# TIDA-010042-E2_Power_Stage_Pg3.net
KiCad netlist of a schematic drawn in Altium Designer
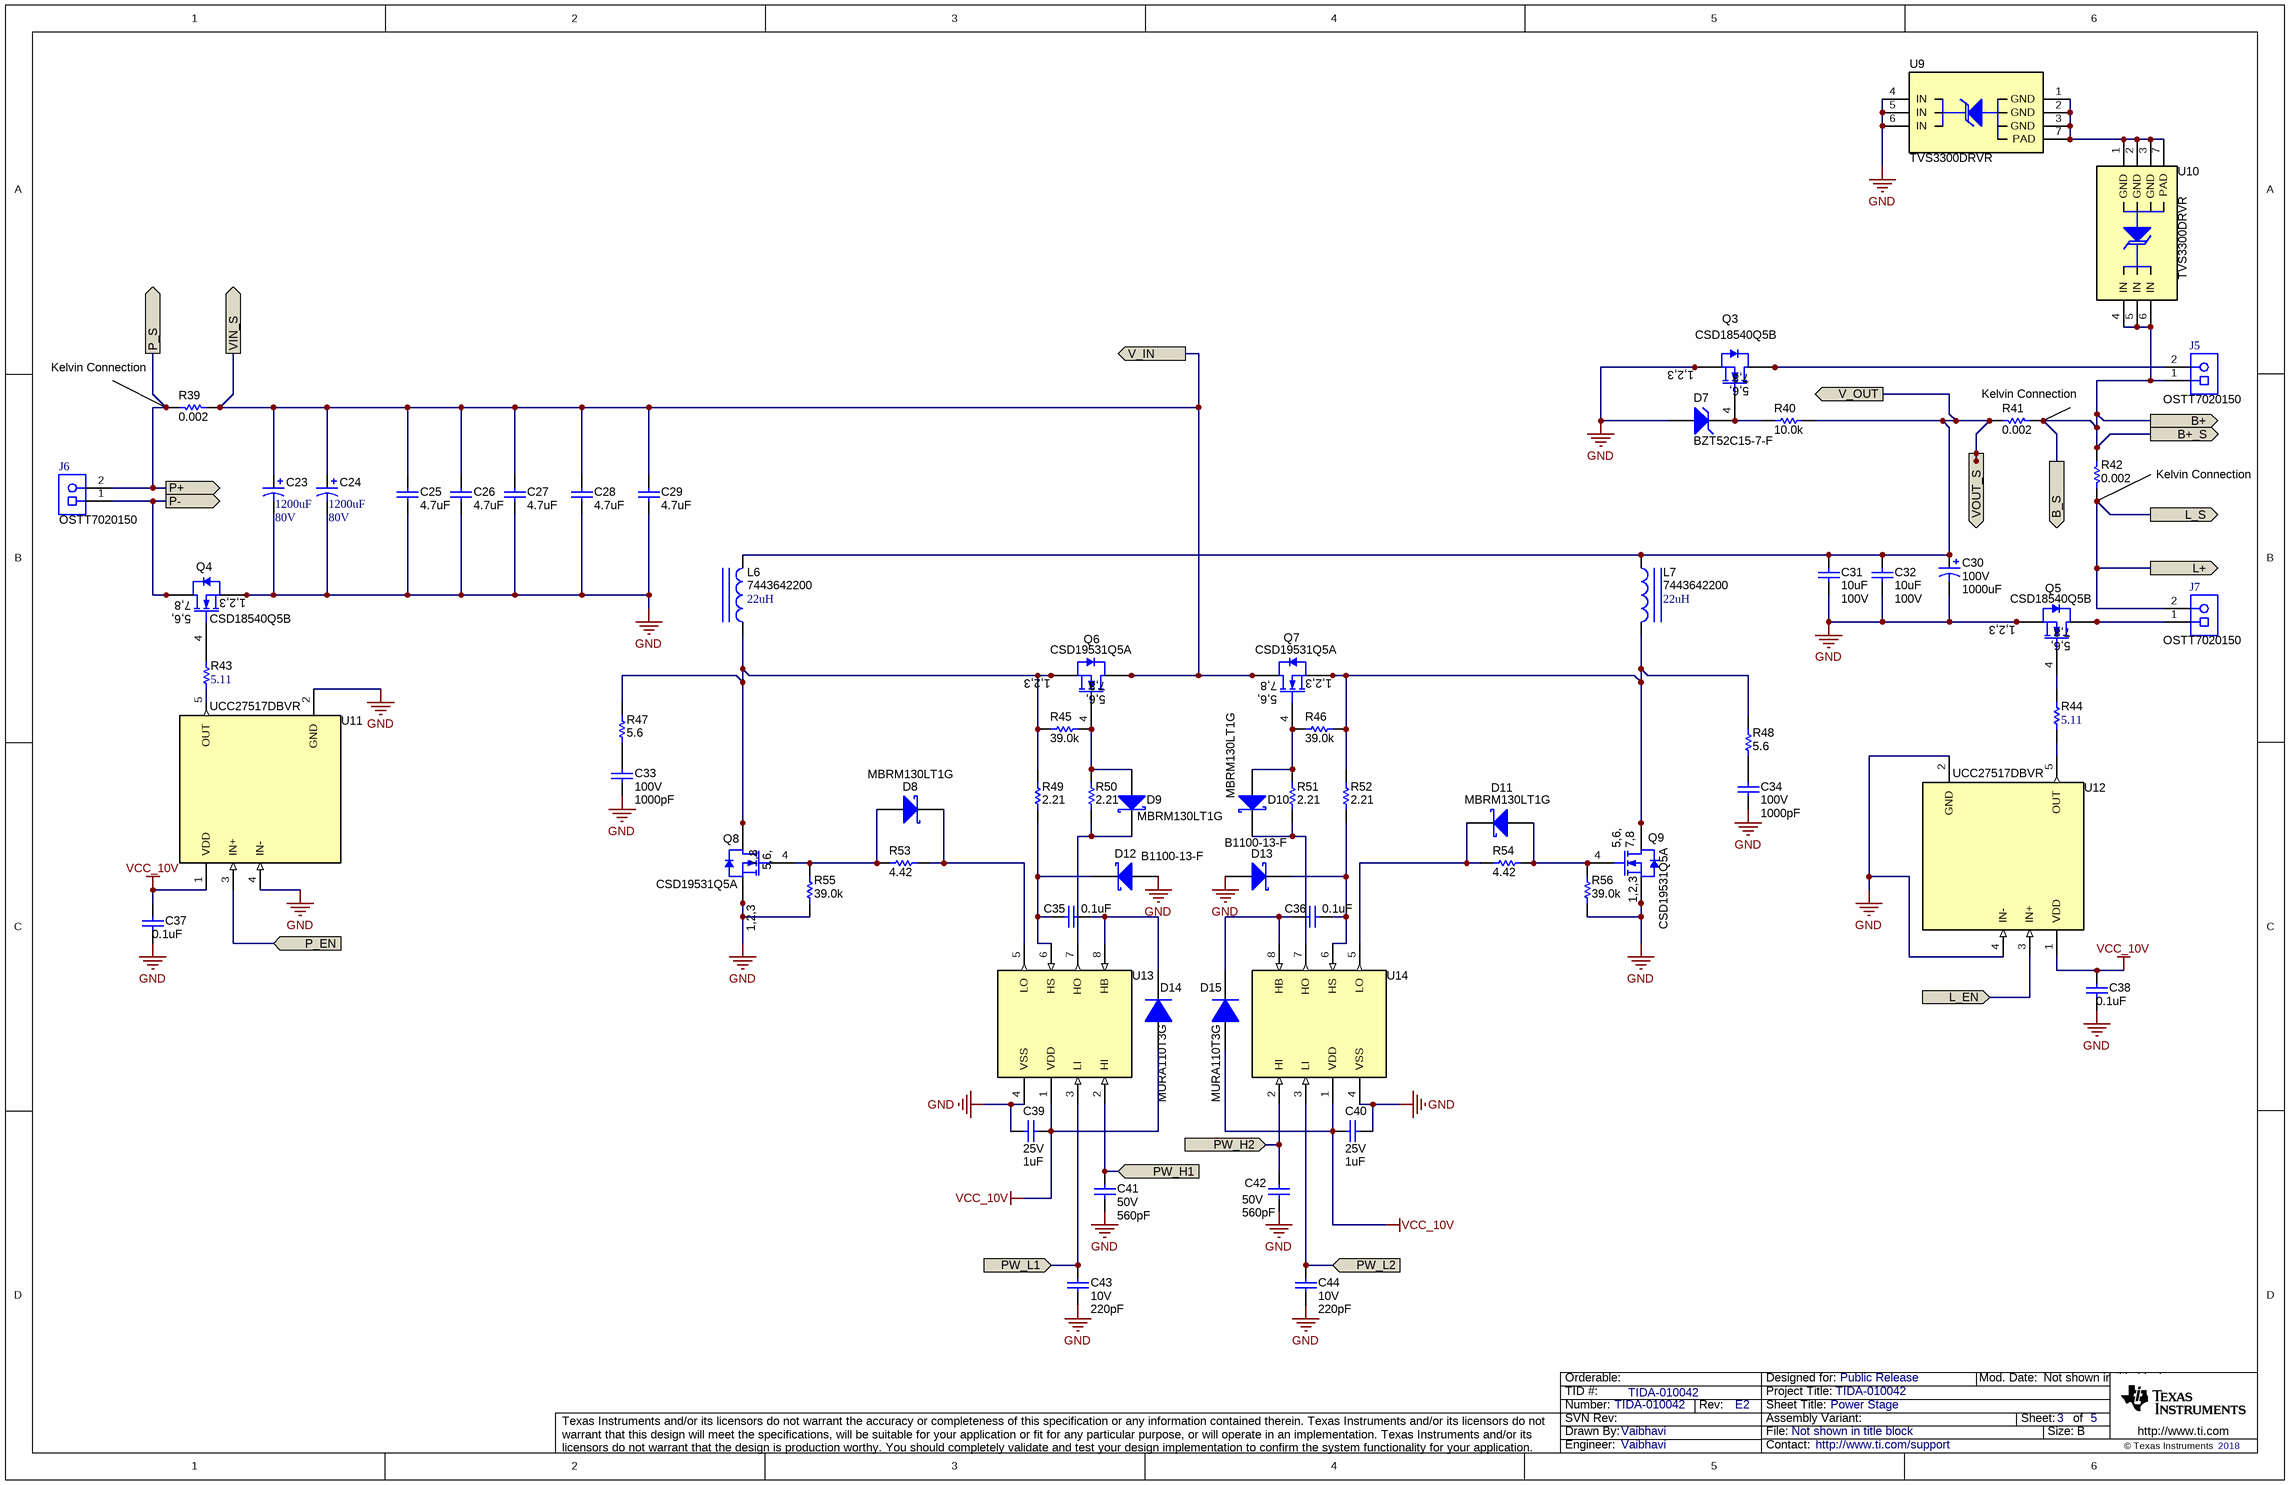
[diagram p0: TIDA-010042-E2_Power Stage_Pg3.SchDoc]

(export (version "E")
  (design (tool "Eeschema 10.0.6"))
  (components
    (comp (ref "C23")
      (value "1200uF")
      (footprint "KYB_1800x3150")
      (description "CAP, AL, 1200 uF, 80 V, +/- 20%, 0.02 ohm, TH")
      (fields
        (field (name "MANUFACTURER") "Chemi-Con")
        (field (name "PARTNUMBER") "EKYB800ELL122MMN3S")
        (field (name "VDC_V") "80V")
        (field (name "PUBLISHER") "Texas Instruments")
      )
      (libsource (lib "Altium Vault - TI") (part "CMP-0009878-2"))
    )
    (comp (ref "C24")
      (value "1200uF")
      (footprint "KYB_1800x3150")
      (description "CAP, AL, 1200 uF, 80 V, +/- 20%, 0.02 ohm, TH")
      (fields
        (field (name "MANUFACTURER") "Chemi-Con")
        (field (name "PARTNUMBER") "EKYB800ELL122MMN3S")
        (field (name "VDC_V") "80V")
        (field (name "PUBLISHER") "Texas Instruments")
      )
      (libsource (lib "Altium Vault - TI") (part "CMP-0009878-2"))
    )
    (comp (ref "C25")
      (value "Capacitor")
      (footprint "2220_250")
      (description "CAP, CERM, 4.7 uF, 100 V, +/- 20%, X7R, AEC-Q200 Grade 1,")
      (fields
        (field (name "PARTNUMBER") "CGA9N2X7R2A475M230KA")
        (field (name "VALUEDISPLAYED") "4.7uF")
        (field (name "MANUFACTURER") "TDK")
        (field (name "PUBLISHER") "Texas Instruments")
      )
      (libsource (lib "Altium Vault - TI") (part "Capacitor"))
    )
    (comp (ref "C26")
      (value "Capacitor")
      (footprint "2220_250")
      (description "CAP, CERM, 4.7 uF, 100 V, +/- 20%, X7R, AEC-Q200 Grade 1,")
      (fields
        (field (name "PARTNUMBER") "CGA9N2X7R2A475M230KA")
        (field (name "VALUEDISPLAYED") "4.7uF")
        (field (name "MANUFACTURER") "TDK")
        (field (name "PUBLISHER") "Texas Instruments")
      )
      (libsource (lib "Altium Vault - TI") (part "Capacitor"))
    )
    (comp (ref "C27")
      (value "Capacitor")
      (footprint "2220_250")
      (description "CAP, CERM, 4.7 uF, 100 V, +/- 20%, X7R, AEC-Q200 Grade 1,")
      (fields
        (field (name "PARTNUMBER") "CGA9N2X7R2A475M230KA")
        (field (name "VALUEDISPLAYED") "4.7uF")
        (field (name "MANUFACTURER") "TDK")
        (field (name "PUBLISHER") "Texas Instruments")
      )
      (libsource (lib "Altium Vault - TI") (part "Capacitor"))
    )
    (comp (ref "C28")
      (value "Capacitor")
      (footprint "2220_250")
      (description "CAP, CERM, 4.7 uF, 100 V, +/- 20%, X7R, AEC-Q200 Grade 1,")
      (fields
        (field (name "PARTNUMBER") "CGA9N2X7R2A475M230KA")
        (field (name "VALUEDISPLAYED") "4.7uF")
        (field (name "MANUFACTURER") "TDK")
        (field (name "PUBLISHER") "Texas Instruments")
      )
      (libsource (lib "Altium Vault - TI") (part "Capacitor"))
    )
    (comp (ref "C29")
      (value "Capacitor")
      (footprint "2220_250")
      (description "CAP, CERM, 4.7 uF, 100 V, +/- 20%, X7R, AEC-Q200 Grade 1,")
      (fields
        (field (name "PARTNUMBER") "CGA9N2X7R2A475M230KA")
        (field (name "VALUEDISPLAYED") "4.7uF")
        (field (name "MANUFACTURER") "TDK")
        (field (name "PUBLISHER") "Texas Instruments")
      )
      (libsource (lib "Altium Vault - TI") (part "Capacitor"))
    )
    (comp (ref "C30")
      (value "UVR2A102MHD")
      (footprint "VR_1800x4000")
      (description "CAP, AL, 1000 uF, 100 V, +/- 20%, TH")
      (fields
        (field (name "MANUFACTURER") "Nichicon")
        (field (name "VDC_V") "100V")
        (field (name "VALUEDISPLAYED") "1000uF")
        (field (name "PUBLISHER") "Texas Instruments")
      )
      (libsource (lib "Altium Vault - TI") (part "Cap_Polarized"))
    )
    (comp (ref "C31")
      (value "22201C106MAT2A")
      (footprint "2220_280")
      (description "CAP, CERM, 10 uF, 100 V, +/- 20%, X7R, 2220")
      (fields
        (field (name "VALUEDISPLAYED") "10uF")
        (field (name "MANUFACTURER") "AVX")
        (field (name "VDC_V") "100V")
        (field (name "PUBLISHER") "Texas Instruments")
      )
      (libsource (lib "Altium Vault - TI") (part "Capacitor"))
    )
    (comp (ref "C32")
      (value "22201C106MAT2A")
      (footprint "2220_280")
      (description "CAP, CERM, 10 uF, 100 V, +/- 20%, X7R, 2220")
      (fields
        (field (name "VALUEDISPLAYED") "10uF")
        (field (name "MANUFACTURER") "AVX")
        (field (name "VDC_V") "100V")
        (field (name "PUBLISHER") "Texas Instruments")
      )
      (libsource (lib "Altium Vault - TI") (part "Capacitor"))
    )
    (comp (ref "C33")
      (value "06031C102JAT2A")
      (footprint "0603")
      (description "CAP, CERM, 1000 pF, 100 V, +/- 5%, X7R, 0603")
      (fields
        (field (name "MANUFACTURER") "AVX")
        (field (name "VDC_V") "100V")
        (field (name "VALUEDISPLAYED") "1000pF")
        (field (name "PUBLISHER") "Texas Instruments")
      )
      (libsource (lib "Altium Vault - TI") (part "Capacitor"))
    )
    (comp (ref "C34")
      (value "06031C102JAT2A")
      (footprint "0603")
      (description "CAP, CERM, 1000 pF, 100 V, +/- 5%, X7R, 0603")
      (fields
        (field (name "MANUFACTURER") "AVX")
        (field (name "VDC_V") "100V")
        (field (name "VALUEDISPLAYED") "1000pF")
        (field (name "PUBLISHER") "Texas Instruments")
      )
      (libsource (lib "Altium Vault - TI") (part "Capacitor"))
    )
    (comp (ref "C35")
      (value "C0805C104K3RACAUTO")
      (footprint "0805_HV")
      (description "CAP CER 0.1UF 16V X7R 0805")
      (fields
        (field (name "MANUFACTURER") "Wurth Electronics Inc.")
        (field (name "PARTNUMBER") "885012207045")
        (field (name "VALUEDISPLAYED") "0.1uF")
        (field (name "PUBLISHER") "Texas Instruments")
      )
      (libsource (lib "Altium Vault - TI") (part "CMP-0007567-2"))
    )
    (comp (ref "C36")
      (value "C0805C104K3RACAUTO")
      (footprint "0805_HV")
      (description "CAP CER 0.1UF 16V X7R 0805")
      (fields
        (field (name "MANUFACTURER") "Wurth Electronics Inc.")
        (field (name "PARTNUMBER") "885012207045")
        (field (name "VALUEDISPLAYED") "0.1uF")
        (field (name "PUBLISHER") "Texas Instruments")
      )
      (libsource (lib "Altium Vault - TI") (part "CMP-0007567-2"))
    )
    (comp (ref "C37")
      (value "GMK107BJ104KAHT")
      (footprint "0603")
      (description "CAP CER 0.1UF 25V X5R 0603")
      (fields
        (field (name "MANUFACTURER") "Taiyo Yuden")
        (field (name "PARTNUMBER") "TMK107BJ104KA-T")
        (field (name "VALUEDISPLAYED") "0.1uF")
        (field (name "PUBLISHER") "Texas Instruments")
      )
      (libsource (lib "Altium Vault - TI") (part "CMP-0007044-5"))
    )
    (comp (ref "C38")
      (value "GMK107BJ104KAHT")
      (footprint "0603")
      (description "CAP CER 0.1UF 25V X5R 0603")
      (fields
        (field (name "MANUFACTURER") "Taiyo Yuden")
        (field (name "PARTNUMBER") "TMK107BJ104KA-T")
        (field (name "VALUEDISPLAYED") "0.1uF")
        (field (name "PUBLISHER") "Texas Instruments")
      )
      (libsource (lib "Altium Vault - TI") (part "CMP-0007044-5"))
    )
    (comp (ref "C39")
      (value "08053C105KAT2A")
      (footprint "0805_HV")
      (description "CAP CER 1UF 25V X7R 0805")
      (fields
        (field (name "MANUFACTURER") "Wurth Electronics Inc.")
        (field (name "PARTNUMBER") "885012207078")
        (field (name "VDC_V") "25V")
        (field (name "VALUEDISPLAYED") "1uF")
        (field (name "PUBLISHER") "Texas Instruments")
      )
      (libsource (lib "Altium Vault - TI") (part "CMP-0007728-2"))
    )
    (comp (ref "C40")
      (value "08053C105KAT2A")
      (footprint "0805_HV")
      (description "CAP CER 1UF 25V X7R 0805")
      (fields
        (field (name "MANUFACTURER") "Wurth Electronics Inc.")
        (field (name "PARTNUMBER") "885012207078")
        (field (name "VDC_V") "25V")
        (field (name "VALUEDISPLAYED") "1uF")
        (field (name "PUBLISHER") "Texas Instruments")
      )
      (libsource (lib "Altium Vault - TI") (part "CMP-0007728-2"))
    )
    (comp (ref "C41")
      (value "C0603C561J5GACTU")
      (footprint "0603")
      (description "CAP, CERM, 560 pF, 50 V, +/- 5%, C0G/NP0, 0603")
      (fields
        (field (name "MANUFACTURER") "Kemet")
        (field (name "VDC_V") "50V")
        (field (name "VALUEDISPLAYED") "560pF")
        (field (name "PUBLISHER") "Texas Instruments")
      )
      (libsource (lib "Altium Vault - TI") (part "Capacitor"))
    )
    (comp (ref "C42")
      (value "C0603C561J5GACTU")
      (footprint "0603")
      (description "CAP, CERM, 560 pF, 50 V, +/- 5%, C0G/NP0, 0603")
      (fields
        (field (name "MANUFACTURER") "Kemet")
        (field (name "VDC_V") "50V")
        (field (name "VALUEDISPLAYED") "560pF")
        (field (name "PUBLISHER") "Texas Instruments")
      )
      (libsource (lib "Altium Vault - TI") (part "Capacitor"))
    )
    (comp (ref "C43")
      (value "CL10C221FB8NNNC")
      (footprint "0603")
      (description "CAP CER 220PF 10V C0G/NP0 0603")
      (fields
        (field (name "MANUFACTURER") "Wurth Electronics Inc.")
        (field (name "PARTNUMBER") "885012006010")
        (field (name "VDC_V") "10V")
        (field (name "VALUEDISPLAYED") "220pF")
        (field (name "PUBLISHER") "Texas Instruments")
      )
      (libsource (lib "Altium Vault - TI") (part "CMP-0007197-4"))
    )
    (comp (ref "C44")
      (value "CL10C221FB8NNNC")
      (footprint "0603")
      (description "CAP CER 220PF 10V C0G/NP0 0603")
      (fields
        (field (name "MANUFACTURER") "Wurth Electronics Inc.")
        (field (name "PARTNUMBER") "885012006010")
        (field (name "VDC_V") "10V")
        (field (name "VALUEDISPLAYED") "220pF")
        (field (name "PUBLISHER") "Texas Instruments")
      )
      (libsource (lib "Altium Vault - TI") (part "CMP-0007197-4"))
    )
    (comp (ref "D7")
      (value "BZT52C15-7-F")
      (footprint "SOD-123")
      (description "Diode, Zener, 15 V, 370 mW, AEC-Q101, SOD-123")
      (fields (field (name "MANUFACTURER") "Diodes Inc.") (field (name "PUBLISHER") "Texas Instruments"))
      (libsource (lib "Altium Vault - TI") (part "Zener"))
    )
    (comp (ref "D8")
      (value "MBRM130LT1G")
      (footprint "POWERMITE")
      (description "Diode, Schottky, 30 V, 1 A, POWERMITE")
      (fields (field (name "MANUFACTURER") "ON Semiconductor") (field (name "PUBLISHER") "Texas Instruments"))
      (libsource (lib "Altium Vault - TI") (part "DIODE_SCHOTTKY"))
    )
    (comp (ref "D9")
      (value "MBRM130LT1G")
      (footprint "POWERMITE")
      (description "Diode, Schottky, 30 V, 1 A, POWERMITE")
      (fields (field (name "MANUFACTURER") "ON Semiconductor") (field (name "PUBLISHER") "Texas Instruments"))
      (libsource (lib "Altium Vault - TI") (part "DIODE_SCHOTTKY"))
    )
    (comp (ref "D10")
      (value "MBRM130LT1G")
      (footprint "POWERMITE")
      (description "Diode, Schottky, 30 V, 1 A, POWERMITE")
      (fields (field (name "MANUFACTURER") "ON Semiconductor") (field (name "PUBLISHER") "Texas Instruments"))
      (libsource (lib "Altium Vault - TI") (part "DIODE_SCHOTTKY"))
    )
    (comp (ref "D11")
      (value "MBRM130LT1G")
      (footprint "POWERMITE")
      (description "Diode, Schottky, 30 V, 1 A, POWERMITE")
      (fields (field (name "MANUFACTURER") "ON Semiconductor") (field (name "PUBLISHER") "Texas Instruments"))
      (libsource (lib "Altium Vault - TI") (part "DIODE_SCHOTTKY"))
    )
    (comp (ref "D12")
      (value "B1100-13-F")
      (footprint "SMA")
      (description "Diode, Schottky, 100 V, 1 A, SMA")
      (fields (field (name "MANUFACTURER") "Diodes Inc.") (field (name "PUBLISHER") "Texas Instruments"))
      (libsource (lib "Altium Vault - TI") (part "DIODE_SCHOTTKY"))
    )
    (comp (ref "D13")
      (value "B1100-13-F")
      (footprint "SMA")
      (description "Diode, Schottky, 100 V, 1 A, SMA")
      (fields (field (name "MANUFACTURER") "Diodes Inc.") (field (name "PUBLISHER") "Texas Instruments"))
      (libsource (lib "Altium Vault - TI") (part "DIODE_SCHOTTKY"))
    )
    (comp (ref "D14")
      (value "MURA110T3G")
      (footprint "SMA")
      (description "Diode, Ultrafast, 100 V, 2 A, SMA")
      (fields (field (name "MANUFACTURER") "ON Semiconductor") (field (name "PUBLISHER") "Texas Instruments"))
      (libsource (lib "Altium Vault - TI") (part "DIODE"))
    )
    (comp (ref "D15")
      (value "MURA110T3G")
      (footprint "SMA")
      (description "Diode, Ultrafast, 100 V, 2 A, SMA")
      (fields (field (name "MANUFACTURER") "ON Semiconductor") (field (name "PUBLISHER") "Texas Instruments"))
      (libsource (lib "Altium Vault - TI") (part "DIODE"))
    )
    (comp (ref "J5")
      (value "OSTT7020150")
      (footprint "On-Shore_OSTT7020150")
      (description "Terminal Block, 6.35mm, 2x1, TH")
      (fields
        (field (name "MANUFACTURER") "On-Shore Technology")
        (field (name "PUBLISHER") "Texas Instruments")
      )
      (libsource (lib "Altium Vault - TI") (part "Receptacle_2x1"))
    )
    (comp (ref "J6")
      (value "OSTT7020150")
      (footprint "On-Shore_OSTT7020150")
      (description "Terminal Block, 6.35mm, 2x1, TH")
      (fields
        (field (name "MANUFACTURER") "On-Shore Technology")
        (field (name "PUBLISHER") "Texas Instruments")
      )
      (libsource (lib "") (part "Receptacle_2x1_1"))
    )
    (comp (ref "J7")
      (value "OSTT7020150")
      (footprint "On-Shore_OSTT7020150")
      (description "Terminal Block, 6.35mm, 2x1, TH")
      (fields
        (field (name "MANUFACTURER") "On-Shore Technology")
        (field (name "PUBLISHER") "Texas Instruments")
      )
      (libsource (lib "Altium Vault - TI") (part "Receptacle_2x1"))
    )
    (comp (ref "L6")
      (value "7443642200")
      (footprint "WE-HCF_2818")
      (description "Inductor, Shielded, Ferrite, 22 uH, 18 A, 0.00264 ohm, SMD")
      (fields
        (field (name "MANUFACTURER") "Wurth Elektronik")
        (field (name "VALUEDISPLAYED") "22uH")
        (field (name "PUBLISHER") "Texas Instruments")
      )
      (libsource (lib "Altium Vault - TI") (part "CMP-0064487-2"))
    )
    (comp (ref "L7")
      (value "7443642200")
      (footprint "WE-HCF_2818")
      (description "Inductor, Shielded, Ferrite, 22 uH, 18 A, 0.00264 ohm, SMD")
      (fields
        (field (name "MANUFACTURER") "Wurth Elektronik")
        (field (name "VALUEDISPLAYED") "22uH")
        (field (name "PUBLISHER") "Texas Instruments")
      )
      (libsource (lib "Altium Vault - TI") (part "CMP-0064487-2"))
    )
    (comp (ref "Q3")
      (value "CSD18540Q5B")
      (footprint "DNK0008A")
      (description "MOSFET, N-CH, 60 V, 100 A, DNK0008A (VSON-CLIP-8)")
      (fields (field (name "MANUFACTURER") "Texas Instruments"))
      (libsource (lib "Altium Vault - TI") (part "MOSFET_N_D56789G4S123"))
    )
    (comp (ref "Q4")
      (value "CSD18540Q5B")
      (footprint "DNK0008A")
      (description "MOSFET, N-CH, 60 V, 100 A, DNK0008A (VSON-CLIP-8)")
      (fields (field (name "MANUFACTURER") "Texas Instruments"))
      (libsource (lib "Altium Vault - TI") (part "MOSFET_N_D56789G4S123"))
    )
    (comp (ref "Q5")
      (value "CSD18540Q5B")
      (footprint "DNK0008A")
      (description "MOSFET, N-CH, 60 V, 100 A, DNK0008A (VSON-CLIP-8)")
      (fields (field (name "MANUFACTURER") "Texas Instruments"))
      (libsource (lib "Altium Vault - TI") (part "MOSFET_N_D56789G4S123"))
    )
    (comp (ref "Q6")
      (value "CSD19531Q5A")
      (footprint "DQJ0008A")
      (description "MOSFET, N-CH, 100 V, 16 A, DQJ0008A (VSONP-8)")
      (fields
        (field (name "MANUFACTURER") "Texas Instruments")
        (field (name "PUBLISHER") "Texas Instruments")
      )
      (libsource (lib "Altium Vault - TI") (part "CMP-0000956-2"))
    )
    (comp (ref "Q7")
      (value "CSD19531Q5A")
      (footprint "DQJ0008A")
      (description "MOSFET, N-CH, 100 V, 16 A, DQJ0008A (VSONP-8)")
      (fields
        (field (name "MANUFACTURER") "Texas Instruments")
        (field (name "PUBLISHER") "Texas Instruments")
      )
      (libsource (lib "Altium Vault - TI") (part "CMP-0000956-2"))
    )
    (comp (ref "Q8")
      (value "CSD19531Q5A")
      (footprint "DQJ0008A")
      (description "MOSFET, N-CH, 100 V, 16 A, DQJ0008A (VSONP-8)")
      (fields
        (field (name "MANUFACTURER") "Texas Instruments")
        (field (name "PUBLISHER") "Texas Instruments")
      )
      (libsource (lib "Altium Vault - TI") (part "CMP-0000956-2"))
    )
    (comp (ref "Q9")
      (value "CSD19531Q5A")
      (footprint "DQJ0008A")
      (description "MOSFET, N-CH, 100 V, 16 A, DQJ0008A (VSONP-8)")
      (fields
        (field (name "MANUFACTURER") "Texas Instruments")
        (field (name "PUBLISHER") "Texas Instruments")
      )
      (libsource (lib "Altium Vault - TI") (part "CMP-0000956-2"))
    )
    (comp (ref "R39")
      (value "CSR2512C0R002F")
      (footprint "LRMA2512_under3")
      (description "RES 0.002 OHM 1% 3W 2512")
      (fields
        (field (name "MANUFACTURER") "Bourns Inc.")
        (field (name "PARTNUMBER") "CRE2512-FZ-R002E-3")
        (field (name "VALUEDISPLAYED") "0.002")
        (field (name "PUBLISHER") "Texas Instruments")
      )
      (libsource (lib "Altium Vault - TI") (part "CMP-0015826-2"))
    )
    (comp (ref "R40")
      (value "Resistor")
      (footprint "0603")
      (description "RES, 10.0 k, 0.1%, 0.1 W, 0603")
      (fields
        (field (name "PARTNUMBER") "RG1608P-103-B-T5")
        (field (name "VALUEDISPLAYED") "10.0k")
        (field (name "MANUFACTURER") "Susumu Co Ltd")
        (field (name "PUBLISHER") "Texas Instruments")
      )
      (libsource (lib "Altium Vault - TI") (part "Resistor"))
    )
    (comp (ref "R41")
      (value "CSR2512C0R002F")
      (footprint "LRMA2512_under3")
      (description "RES 0.002 OHM 1% 3W 2512")
      (fields
        (field (name "MANUFACTURER") "Bourns Inc.")
        (field (name "PARTNUMBER") "CRE2512-FZ-R002E-3")
        (field (name "VALUEDISPLAYED") "0.002")
        (field (name "PUBLISHER") "Texas Instruments")
      )
      (libsource (lib "Altium Vault - TI") (part "CMP-0015826-2"))
    )
    (comp (ref "R42")
      (value "CSR2512C0R002F")
      (footprint "LRMA2512_under3")
      (description "RES 0.002 OHM 1% 3W 2512")
      (fields
        (field (name "MANUFACTURER") "Bourns Inc.")
        (field (name "PARTNUMBER") "CRE2512-FZ-R002E-3")
        (field (name "VALUEDISPLAYED") "0.002")
        (field (name "PUBLISHER") "Texas Instruments")
      )
      (libsource (lib "Altium Vault - TI") (part "CMP-0015826-2"))
    )
    (comp (ref "R43")
      (value "5.11")
      (footprint "1206")
      (description "RES, 5.11, 1%, 0.25 W, AEC-Q200 Grade 0, 1206")
      (fields (field (name "MANUFACTURER") "Vishay-Dale") (field (name "PARTNUMBER") "CRCW12065R11FKEA"))
      (libsource (lib "Altium Vault - TI") (part "CMP-0017092-3"))
    )
    (comp (ref "R44")
      (value "5.11")
      (footprint "1206")
      (description "RES, 5.11, 1%, 0.25 W, AEC-Q200 Grade 0, 1206")
      (fields (field (name "MANUFACTURER") "Vishay-Dale") (field (name "PARTNUMBER") "CRCW12065R11FKEA"))
      (libsource (lib "Altium Vault - TI") (part "CMP-0017092-3"))
    )
    (comp (ref "R45")
      (value "CRCW080539R0JNEA")
      (footprint "0805_HV")
      (description "RES, 39.0 k, 1%, 0.2 W, 0805")
      (fields
        (field (name "MANUFACTURER") "Vishay-Dale")
        (field (name "VALUEDISPLAYED") "39.0k")
        (field (name "PUBLISHER") "Texas Instruments")
      )
      (libsource (lib "Altium Vault - TI") (part "CMP-0021860-2"))
    )
    (comp (ref "R46")
      (value "CRCW080539R0JNEA")
      (footprint "0805_HV")
      (description "RES, 39.0 k, 1%, 0.2 W, 0805")
      (fields
        (field (name "MANUFACTURER") "Vishay-Dale")
        (field (name "VALUEDISPLAYED") "39.0k")
        (field (name "PUBLISHER") "Texas Instruments")
      )
      (libsource (lib "Altium Vault - TI") (part "CMP-0021860-2"))
    )
    (comp (ref "R47")
      (value "Resistor")
      (footprint "2512")
      (description "RES, 5.6, 5%, 1 W, AEC-Q200 Grade 0, 2512")
      (fields
        (field (name "PARTNUMBER") "CRCW25125R60JNEG")
        (field (name "VALUEDISPLAYED") "5.6")
        (field (name "MANUFACTURER") "Vishay-Dale")
      )
      (libsource (lib "Altium Vault - TI") (part "Resistor"))
    )
    (comp (ref "R48")
      (value "Resistor")
      (footprint "2512")
      (description "RES, 5.6, 5%, 1 W, AEC-Q200 Grade 0, 2512")
      (fields
        (field (name "PARTNUMBER") "CRCW25125R60JNEG")
        (field (name "VALUEDISPLAYED") "5.6")
        (field (name "MANUFACTURER") "Vishay-Dale")
      )
      (libsource (lib "Altium Vault - TI") (part "Resistor"))
    )
    (comp (ref "R49")
      (value "CRCW08052R21FKEA")
      (footprint "0805_HV")
      (description "RES, 2.21, 1%, 0.125 W, AEC-Q200 Grade 0, 0805")
      (fields (field (name "MANUFACTURER") "Vishay-Dale") (field (name "VALUEDISPLAYED") "2.21"))
      (libsource (lib "Altium Vault - TI") (part "Resistor"))
    )
    (comp (ref "R50")
      (value "CRCW08052R21FKEA")
      (footprint "0805_HV")
      (description "RES, 2.21, 1%, 0.125 W, AEC-Q200 Grade 0, 0805")
      (fields (field (name "MANUFACTURER") "Vishay-Dale") (field (name "VALUEDISPLAYED") "2.21"))
      (libsource (lib "Altium Vault - TI") (part "Resistor"))
    )
    (comp (ref "R51")
      (value "CRCW08052R21FKEA")
      (footprint "0805_HV")
      (description "RES, 2.21, 1%, 0.125 W, AEC-Q200 Grade 0, 0805")
      (fields (field (name "MANUFACTURER") "Vishay-Dale") (field (name "VALUEDISPLAYED") "2.21"))
      (libsource (lib "Altium Vault - TI") (part "Resistor"))
    )
    (comp (ref "R52")
      (value "CRCW08052R21FKEA")
      (footprint "0805_HV")
      (description "RES, 2.21, 1%, 0.125 W, AEC-Q200 Grade 0, 0805")
      (fields (field (name "MANUFACTURER") "Vishay-Dale") (field (name "VALUEDISPLAYED") "2.21"))
      (libsource (lib "Altium Vault - TI") (part "Resistor"))
    )
    (comp (ref "R53")
      (value "RC0805FR-074R42L")
      (footprint "0805_HV")
      (description "RES, 4.42, 1%, 0.125 W, 0805")
      (fields
        (field (name "MANUFACTURER") "Yageo America")
        (field (name "VALUEDISPLAYED") "4.42")
        (field (name "PUBLISHER") "Texas Instruments")
      )
      (libsource (lib "Altium Vault - TI") (part "Resistor"))
    )
    (comp (ref "R54")
      (value "RC0805FR-074R42L")
      (footprint "0805_HV")
      (description "RES, 4.42, 1%, 0.125 W, 0805")
      (fields
        (field (name "MANUFACTURER") "Yageo America")
        (field (name "VALUEDISPLAYED") "4.42")
        (field (name "PUBLISHER") "Texas Instruments")
      )
      (libsource (lib "Altium Vault - TI") (part "Resistor"))
    )
    (comp (ref "R55")
      (value "CRCW080539R0JNEA")
      (footprint "0805_HV")
      (description "RES, 39.0 k, 1%, 0.2 W, 0805")
      (fields
        (field (name "MANUFACTURER") "Vishay-Dale")
        (field (name "VALUEDISPLAYED") "39.0k")
        (field (name "PUBLISHER") "Texas Instruments")
      )
      (libsource (lib "Altium Vault - TI") (part "CMP-0021860-2"))
    )
    (comp (ref "R56")
      (value "CRCW080539R0JNEA")
      (footprint "0805_HV")
      (description "RES, 39.0 k, 1%, 0.2 W, 0805")
      (fields
        (field (name "MANUFACTURER") "Vishay-Dale")
        (field (name "VALUEDISPLAYED") "39.0k")
        (field (name "PUBLISHER") "Texas Instruments")
      )
      (libsource (lib "Altium Vault - TI") (part "CMP-0021860-2"))
    )
    (comp (ref "U9")
      (value "TVS3300DRVR")
      (footprint "DRV0006A")
      (description "33-V Precision Surge Protection Clamp, DRV0006A (WSON-6)")
      (fields
        (field (name "PARTNUMBER") "TVS3300DRVR")
        (field (name "MANUFACTURER") "Texas Instruments")
        (field (name "ALTERNATE PARTNUMBER") "TVS3300DRVT")
      )
      (libsource (lib "") (part "CMP-0013424-7_1"))
    )
    (comp (ref "U10")
      (value "TVS3300DRVR")
      (footprint "DRV0006A")
      (description "33-V Precision Surge Protection Clamp, DRV0006A (WSON-6)")
      (fields
        (field (name "PARTNUMBER") "TVS3300DRVR")
        (field (name "MANUFACTURER") "Texas Instruments")
        (field (name "ALTERNATE PARTNUMBER") "TVS3300DRVT")
      )
      (libsource (lib "Altium Vault - TI") (part "CMP-0013424-7"))
    )
    (comp (ref "U11")
      (value "UCC27517DBVR")
      (footprint "DBV0005A_N")
      (description "4A/4A Single Channel High-speed Low-side Gate Driver, DBV0005A (SOT-23-5)")
      (fields
        (field (name "ALTERNATE PARTNUMBER") "UCC27517DBVT")
        (field (name "MANUFACTURER") "Texas Instruments")
        (field (name "PARTNUMBER") "UCC27517DBVR")
        (field (name "PUBLISHER") "Texas Instruments")
      )
      (libsource (lib "") (part "CMP-0066947-1_1"))
    )
    (comp (ref "U12")
      (value "UCC27517DBVR")
      (footprint "DBV0005A_N")
      (description "4A/4A Single Channel High-speed Low-side Gate Driver, DBV0005A (SOT-23-5)")
      (fields
        (field (name "ALTERNATE PARTNUMBER") "UCC27517DBVT")
        (field (name "MANUFACTURER") "Texas Instruments")
        (field (name "PARTNUMBER") "UCC27517DBVR")
        (field (name "PUBLISHER") "Texas Instruments")
      )
      (libsource (lib "Altium Vault - TI") (part "CMP-0066947-1"))
    )
    (comp (ref "U13")
      (value "LM5109BMA/NOPB")
      (footprint "D0008A_N")
      (description "High Voltage 1A Peak Half Bridge Gate Driver, 8-pin Narrow SOIC, Pb-Free")
      (fields (field (name "MANUFACTURER") "Texas Instruments"))
      (libsource (lib "Altium Vault - TI") (part "CMP-0071431-1"))
    )
    (comp (ref "U14")
      (value "LM5109BMA/NOPB")
      (footprint "D0008A_N")
      (description "High Voltage 1A Peak Half Bridge Gate Driver, 8-pin Narrow SOIC, Pb-Free")
      (fields (field (name "MANUFACTURER") "Texas Instruments"))
      (libsource (lib "") (part "CMP-0071431-1_1"))
    )
  )
  (nets
    (net (code "1") (name "/B+") (class "Default")
      (node (ref "J5") (pin "1") (pinfunction "1_1") (pintype "passive"))
      (node (ref "R41") (pin "2") (pinfunction "2_2") (pintype "passive"))
      (node (ref "R42") (pin "2") (pinfunction "2_2") (pintype "passive"))
      (node (ref "U10") (pin "4") (pinfunction "IN_4") (pintype "passive"))
      (node (ref "U10") (pin "5") (pinfunction "IN_5") (pintype "passive"))
      (node (ref "U10") (pin "6") (pinfunction "IN_6") (pintype "passive"))
    )
    (net (code "2") (name "/L+") (class "Default")
      (node (ref "J7") (pin "2") (pinfunction "2_2") (pintype "passive"))
      (node (ref "R42") (pin "1") (pinfunction "1_1") (pintype "passive"))
    )
    (net (code "3") (name "/L_EN") (class "Default")
      (node (ref "U12") (pin "3") (pinfunction "IN+_3") (pintype "input"))
    )
    (net (code "4") (name "/P+") (class "Default")
      (node (ref "J6") (pin "2") (pinfunction "2_2") (pintype "passive"))
      (node (ref "R39") (pin "2") (pinfunction "2_2") (pintype "passive"))
    )
    (net (code "5") (name "/P-") (class "Default")
      (node (ref "J6") (pin "1") (pinfunction "1_1") (pintype "passive"))
      (node (ref "Q4") (pin "5") (pinfunction "D_5") (pintype "passive"))
      (node (ref "Q4") (pin "6") (pinfunction "D_6") (pintype "passive"))
      (node (ref "Q4") (pin "7") (pinfunction "D_7") (pintype "passive"))
      (node (ref "Q4") (pin "8") (pinfunction "D_8") (pintype "passive"))
      (node (ref "Q4") (pin "9") (pinfunction "D_9") (pintype "passive"))
    )
    (net (code "6") (name "/PW_H1") (class "Default")
      (node (ref "C41") (pin "1") (pinfunction "1_1") (pintype "passive"))
      (node (ref "U13") (pin "2") (pinfunction "HI_2") (pintype "input"))
    )
    (net (code "7") (name "/PW_H2") (class "Default")
      (node (ref "C42") (pin "1") (pinfunction "1_1") (pintype "passive"))
      (node (ref "U14") (pin "2") (pinfunction "HI_2") (pintype "input"))
    )
    (net (code "8") (name "/PW_L1") (class "Default")
      (node (ref "C43") (pin "1") (pinfunction "1_1") (pintype "passive"))
      (node (ref "U13") (pin "3") (pinfunction "LI_3") (pintype "input"))
    )
    (net (code "9") (name "/PW_L2") (class "Default")
      (node (ref "C44") (pin "1") (pinfunction "1_1") (pintype "passive"))
      (node (ref "U14") (pin "3") (pinfunction "LI_3") (pintype "input"))
    )
    (net (code "10") (name "/P_EN") (class "Default")
      (node (ref "U11") (pin "3") (pinfunction "IN+_3") (pintype "input"))
    )
    (net (code "11") (name "/VIN_S") (class "Default")
      (node (ref "C23") (pin "1") (pinfunction "+_1") (pintype "passive"))
      (node (ref "C24") (pin "1") (pinfunction "+_1") (pintype "passive"))
      (node (ref "C25") (pin "1") (pinfunction "1_1") (pintype "passive"))
      (node (ref "C26") (pin "1") (pinfunction "1_1") (pintype "passive"))
      (node (ref "C27") (pin "1") (pinfunction "1_1") (pintype "passive"))
      (node (ref "C28") (pin "1") (pinfunction "1_1") (pintype "passive"))
      (node (ref "C29") (pin "1") (pinfunction "1_1") (pintype "passive"))
      (node (ref "Q6") (pin "5") (pinfunction "D_5") (pintype "passive"))
      (node (ref "Q6") (pin "6") (pinfunction "D_6") (pintype "passive"))
      (node (ref "Q6") (pin "7") (pinfunction "D_7") (pintype "passive"))
      (node (ref "Q6") (pin "8") (pinfunction "D_8") (pintype "passive"))
      (node (ref "Q6") (pin "9") (pinfunction "D_9") (pintype "passive"))
      (node (ref "Q7") (pin "5") (pinfunction "D_5") (pintype "passive"))
      (node (ref "Q7") (pin "6") (pinfunction "D_6") (pintype "passive"))
      (node (ref "Q7") (pin "7") (pinfunction "D_7") (pintype "passive"))
      (node (ref "Q7") (pin "8") (pinfunction "D_8") (pintype "passive"))
      (node (ref "Q7") (pin "9") (pinfunction "D_9") (pintype "passive"))
      (node (ref "R39") (pin "1") (pinfunction "1_1") (pintype "passive"))
    )
    (net (code "12") (name "/VOUT_S") (class "Default")
      (node (ref "C30") (pin "1") (pinfunction "+_1") (pintype "passive"))
      (node (ref "C31") (pin "1") (pinfunction "1_1") (pintype "passive"))
      (node (ref "C32") (pin "1") (pinfunction "1_1") (pintype "passive"))
      (node (ref "L6") (pin "2") (pinfunction "2_2") (pintype "passive"))
      (node (ref "L7") (pin "1") (pinfunction "1_1") (pintype "passive"))
      (node (ref "R40") (pin "2") (pinfunction "2_2") (pintype "passive"))
      (node (ref "R41") (pin "1") (pinfunction "1_1") (pintype "passive"))
    )
    (net (code "13") (name "GND") (class "Default")
      (node (ref "C23") (pin "2") (pinfunction "-_2") (pintype "passive"))
      (node (ref "C24") (pin "2") (pinfunction "-_2") (pintype "passive"))
      (node (ref "C25") (pin "2") (pinfunction "2_2") (pintype "passive"))
      (node (ref "C26") (pin "2") (pinfunction "2_2") (pintype "passive"))
      (node (ref "C27") (pin "2") (pinfunction "2_2") (pintype "passive"))
      (node (ref "C28") (pin "2") (pinfunction "2_2") (pintype "passive"))
      (node (ref "C29") (pin "2") (pinfunction "2_2") (pintype "passive"))
      (node (ref "C30") (pin "2") (pinfunction "-_2") (pintype "passive"))
      (node (ref "C31") (pin "2") (pinfunction "2_2") (pintype "passive"))
      (node (ref "C32") (pin "2") (pinfunction "2_2") (pintype "passive"))
      (node (ref "C33") (pin "2") (pinfunction "2_2") (pintype "passive"))
      (node (ref "C34") (pin "2") (pinfunction "2_2") (pintype "passive"))
      (node (ref "C37") (pin "2") (pinfunction "2_2") (pintype "passive"))
      (node (ref "C38") (pin "2") (pinfunction "2_2") (pintype "passive"))
      (node (ref "C39") (pin "2") (pinfunction "2_2") (pintype "passive"))
      (node (ref "C40") (pin "1") (pinfunction "1_1") (pintype "passive"))
      (node (ref "C41") (pin "2") (pinfunction "2_2") (pintype "passive"))
      (node (ref "C42") (pin "2") (pinfunction "2_2") (pintype "passive"))
      (node (ref "C43") (pin "2") (pinfunction "2_2") (pintype "passive"))
      (node (ref "C44") (pin "2") (pinfunction "2_2") (pintype "passive"))
      (node (ref "D12") (pin "2") (pinfunction "A_2") (pintype "passive"))
      (node (ref "D13") (pin "2") (pinfunction "A_2") (pintype "passive"))
      (node (ref "D7") (pin "2") (pinfunction "A_2") (pintype "passive"))
      (node (ref "Q3") (pin "1") (pinfunction "S_1") (pintype "passive"))
      (node (ref "Q3") (pin "2") (pinfunction "S_2") (pintype "passive"))
      (node (ref "Q3") (pin "3") (pinfunction "S_3") (pintype "passive"))
      (node (ref "Q4") (pin "1") (pinfunction "S_1") (pintype "passive"))
      (node (ref "Q4") (pin "2") (pinfunction "S_2") (pintype "passive"))
      (node (ref "Q4") (pin "3") (pinfunction "S_3") (pintype "passive"))
      (node (ref "Q5") (pin "1") (pinfunction "S_1") (pintype "passive"))
      (node (ref "Q5") (pin "2") (pinfunction "S_2") (pintype "passive"))
      (node (ref "Q5") (pin "3") (pinfunction "S_3") (pintype "passive"))
      (node (ref "Q8") (pin "1") (pinfunction "S_1") (pintype "passive"))
      (node (ref "Q8") (pin "2") (pinfunction "S_2") (pintype "passive"))
      (node (ref "Q8") (pin "3") (pinfunction "S_3") (pintype "passive"))
      (node (ref "Q9") (pin "1") (pinfunction "S_1") (pintype "passive"))
      (node (ref "Q9") (pin "2") (pinfunction "S_2") (pintype "passive"))
      (node (ref "Q9") (pin "3") (pinfunction "S_3") (pintype "passive"))
      (node (ref "R55") (pin "1") (pinfunction "1_1") (pintype "passive"))
      (node (ref "R56") (pin "2") (pinfunction "2_2") (pintype "passive"))
      (node (ref "U11") (pin "2") (pinfunction "GND_2") (pintype "power_in"))
      (node (ref "U11") (pin "4") (pinfunction "IN-_4") (pintype "input"))
      (node (ref "U12") (pin "2") (pinfunction "GND_2") (pintype "power_in"))
      (node (ref "U12") (pin "4") (pinfunction "IN-_4") (pintype "input"))
      (node (ref "U13") (pin "4") (pinfunction "VSS_4") (pintype "power_in"))
      (node (ref "U14") (pin "4") (pinfunction "VSS_4") (pintype "power_in"))
      (node (ref "U9") (pin "4") (pinfunction "IN_4") (pintype "passive"))
      (node (ref "U9") (pin "5") (pinfunction "IN_5") (pintype "passive"))
      (node (ref "U9") (pin "6") (pinfunction "IN_6") (pintype "passive"))
    )
    (net (code "14") (name "Net-(C33-Pad1)") (class "Default")
      (node (ref "C33") (pin "1") (pinfunction "1_1") (pintype "passive"))
      (node (ref "R47") (pin "1") (pinfunction "1_1") (pintype "passive"))
    )
    (net (code "15") (name "Net-(C34-Pad1)") (class "Default")
      (node (ref "C34") (pin "1") (pinfunction "1_1") (pintype "passive"))
      (node (ref "R48") (pin "1") (pinfunction "1_1") (pintype "passive"))
    )
    (net (code "16") (name "Net-(D7-K)") (class "Default")
      (node (ref "D7") (pin "1") (pinfunction "K_1") (pintype "passive"))
      (node (ref "Q3") (pin "4") (pinfunction "G_4") (pintype "passive"))
      (node (ref "R40") (pin "1") (pinfunction "1_1") (pintype "passive"))
    )
    (net (code "17") (name "Net-(D8-A)") (class "Default")
      (node (ref "D8") (pin "2") (pinfunction "A_2") (pintype "passive"))
      (node (ref "Q8") (pin "4") (pinfunction "G_4") (pintype "passive"))
      (node (ref "R53") (pin "1") (pinfunction "1_1") (pintype "passive"))
      (node (ref "R55") (pin "2") (pinfunction "2_2") (pintype "passive"))
    )
    (net (code "18") (name "Net-(D8-K)") (class "Default")
      (node (ref "D8") (pin "1") (pinfunction "K_1") (pintype "passive"))
      (node (ref "R53") (pin "2") (pinfunction "2_2") (pintype "passive"))
      (node (ref "U13") (pin "5") (pinfunction "LO_5") (pintype "output"))
    )
    (net (code "19") (name "Net-(D9-A)") (class "Default")
      (node (ref "D9") (pin "2") (pinfunction "A_2") (pintype "passive"))
      (node (ref "Q6") (pin "4") (pinfunction "G_4") (pintype "passive"))
      (node (ref "R45") (pin "1") (pinfunction "1_1") (pintype "passive"))
      (node (ref "R50") (pin "2") (pinfunction "2_2") (pintype "passive"))
    )
    (net (code "20") (name "Net-(D9-K)") (class "Default")
      (node (ref "D9") (pin "1") (pinfunction "K_1") (pintype "passive"))
      (node (ref "R50") (pin "1") (pinfunction "1_1") (pintype "passive"))
      (node (ref "U13") (pin "7") (pinfunction "HO_7") (pintype "output"))
    )
    (net (code "21") (name "Net-(D10-A)") (class "Default")
      (node (ref "D10") (pin "2") (pinfunction "A_2") (pintype "passive"))
      (node (ref "Q7") (pin "4") (pinfunction "G_4") (pintype "passive"))
      (node (ref "R46") (pin "2") (pinfunction "2_2") (pintype "passive"))
      (node (ref "R51") (pin "2") (pinfunction "2_2") (pintype "passive"))
    )
    (net (code "22") (name "Net-(D10-K)") (class "Default")
      (node (ref "D10") (pin "1") (pinfunction "K_1") (pintype "passive"))
      (node (ref "R51") (pin "1") (pinfunction "1_1") (pintype "passive"))
      (node (ref "U14") (pin "7") (pinfunction "HO_7") (pintype "output"))
    )
    (net (code "23") (name "Net-(D11-A)") (class "Default")
      (node (ref "D11") (pin "2") (pinfunction "A_2") (pintype "passive"))
      (node (ref "Q9") (pin "4") (pinfunction "G_4") (pintype "passive"))
      (node (ref "R54") (pin "2") (pinfunction "2_2") (pintype "passive"))
      (node (ref "R56") (pin "1") (pinfunction "1_1") (pintype "passive"))
    )
    (net (code "24") (name "Net-(D11-K)") (class "Default")
      (node (ref "D11") (pin "1") (pinfunction "K_1") (pintype "passive"))
      (node (ref "R54") (pin "1") (pinfunction "1_1") (pintype "passive"))
      (node (ref "U14") (pin "5") (pinfunction "LO_5") (pintype "output"))
    )
    (net (code "25") (name "Net-(D12-K)") (class "Default")
      (node (ref "C35") (pin "2") (pinfunction "2_2") (pintype "passive"))
      (node (ref "D12") (pin "1") (pinfunction "K_1") (pintype "passive"))
      (node (ref "R49") (pin "1") (pinfunction "1_1") (pintype "passive"))
      (node (ref "U13") (pin "6") (pinfunction "HS_6") (pintype "input"))
    )
    (net (code "26") (name "Net-(D13-K)") (class "Default")
      (node (ref "C36") (pin "1") (pinfunction "1_1") (pintype "passive"))
      (node (ref "D13") (pin "1") (pinfunction "K_1") (pintype "passive"))
      (node (ref "R52") (pin "1") (pinfunction "1_1") (pintype "passive"))
      (node (ref "U14") (pin "6") (pinfunction "HS_6") (pintype "input"))
    )
    (net (code "27") (name "Net-(D14-K)") (class "Default")
      (node (ref "C35") (pin "1") (pinfunction "1_1") (pintype "passive"))
      (node (ref "D14") (pin "1") (pinfunction "K_1") (pintype "passive"))
      (node (ref "U13") (pin "8") (pinfunction "HB_8") (pintype "input"))
    )
    (net (code "28") (name "Net-(D15-K)") (class "Default")
      (node (ref "C36") (pin "2") (pinfunction "2_2") (pintype "passive"))
      (node (ref "D15") (pin "1") (pinfunction "K_1") (pintype "passive"))
      (node (ref "U14") (pin "8") (pinfunction "HB_8") (pintype "input"))
    )
    (net (code "29") (name "Net-(J5-Pad2)") (class "Default")
      (node (ref "J5") (pin "2") (pinfunction "2_2") (pintype "passive"))
      (node (ref "Q3") (pin "5") (pinfunction "D_5") (pintype "passive"))
      (node (ref "Q3") (pin "6") (pinfunction "D_6") (pintype "passive"))
      (node (ref "Q3") (pin "7") (pinfunction "D_7") (pintype "passive"))
      (node (ref "Q3") (pin "8") (pinfunction "D_8") (pintype "passive"))
      (node (ref "Q3") (pin "9") (pinfunction "D_9") (pintype "passive"))
    )
    (net (code "30") (name "Net-(J7-Pad1)") (class "Default")
      (node (ref "J7") (pin "1") (pinfunction "1_1") (pintype "passive"))
      (node (ref "Q5") (pin "5") (pinfunction "D_5") (pintype "passive"))
      (node (ref "Q5") (pin "6") (pinfunction "D_6") (pintype "passive"))
      (node (ref "Q5") (pin "7") (pinfunction "D_7") (pintype "passive"))
      (node (ref "Q5") (pin "8") (pinfunction "D_8") (pintype "passive"))
      (node (ref "Q5") (pin "9") (pinfunction "D_9") (pintype "passive"))
    )
    (net (code "31") (name "Net-(L6-Pad1)") (class "Default")
      (node (ref "L6") (pin "1") (pinfunction "1_1") (pintype "passive"))
      (node (ref "Q6") (pin "1") (pinfunction "S_1") (pintype "passive"))
      (node (ref "Q6") (pin "2") (pinfunction "S_2") (pintype "passive"))
      (node (ref "Q6") (pin "3") (pinfunction "S_3") (pintype "passive"))
      (node (ref "Q8") (pin "5") (pinfunction "D_5") (pintype "passive"))
      (node (ref "Q8") (pin "6") (pinfunction "D_6") (pintype "passive"))
      (node (ref "Q8") (pin "7") (pinfunction "D_7") (pintype "passive"))
      (node (ref "Q8") (pin "8") (pinfunction "D_8") (pintype "passive"))
      (node (ref "Q8") (pin "9") (pinfunction "D_9") (pintype "passive"))
      (node (ref "R45") (pin "2") (pinfunction "2_2") (pintype "passive"))
      (node (ref "R47") (pin "2") (pinfunction "2_2") (pintype "passive"))
      (node (ref "R49") (pin "2") (pinfunction "2_2") (pintype "passive"))
    )
    (net (code "32") (name "Net-(L7-Pad2)") (class "Default")
      (node (ref "L7") (pin "2") (pinfunction "2_2") (pintype "passive"))
      (node (ref "Q7") (pin "1") (pinfunction "S_1") (pintype "passive"))
      (node (ref "Q7") (pin "2") (pinfunction "S_2") (pintype "passive"))
      (node (ref "Q7") (pin "3") (pinfunction "S_3") (pintype "passive"))
      (node (ref "Q9") (pin "5") (pinfunction "D_5") (pintype "passive"))
      (node (ref "Q9") (pin "6") (pinfunction "D_6") (pintype "passive"))
      (node (ref "Q9") (pin "7") (pinfunction "D_7") (pintype "passive"))
      (node (ref "Q9") (pin "8") (pinfunction "D_8") (pintype "passive"))
      (node (ref "Q9") (pin "9") (pinfunction "D_9") (pintype "passive"))
      (node (ref "R46") (pin "1") (pinfunction "1_1") (pintype "passive"))
      (node (ref "R48") (pin "2") (pinfunction "2_2") (pintype "passive"))
      (node (ref "R52") (pin "2") (pinfunction "2_2") (pintype "passive"))
    )
    (net (code "33") (name "Net-(Q4-G)") (class "Default")
      (node (ref "Q4") (pin "4") (pinfunction "G_4") (pintype "passive"))
      (node (ref "R43") (pin "2") (pinfunction "2_2") (pintype "passive"))
    )
    (net (code "34") (name "Net-(Q5-G)") (class "Default")
      (node (ref "Q5") (pin "4") (pinfunction "G_4") (pintype "passive"))
      (node (ref "R44") (pin "2") (pinfunction "2_2") (pintype "passive"))
    )
    (net (code "35") (name "Net-(U10-PAD)") (class "Default")
      (node (ref "U10") (pin "1") (pinfunction "GND_1") (pintype "passive"))
      (node (ref "U10") (pin "2") (pinfunction "GND_2") (pintype "passive"))
      (node (ref "U10") (pin "3") (pinfunction "GND_3") (pintype "passive"))
      (node (ref "U10") (pin "7") (pinfunction "PAD_7") (pintype "passive"))
      (node (ref "U9") (pin "1") (pinfunction "GND_1") (pintype "passive"))
      (node (ref "U9") (pin "2") (pinfunction "GND_2") (pintype "passive"))
      (node (ref "U9") (pin "3") (pinfunction "GND_3") (pintype "passive"))
      (node (ref "U9") (pin "7") (pinfunction "PAD_7") (pintype "passive"))
    )
    (net (code "36") (name "Net-(U11-OUT)") (class "Default")
      (node (ref "R43") (pin "1") (pinfunction "1_1") (pintype "passive"))
      (node (ref "U11") (pin "5") (pinfunction "OUT_5") (pintype "output"))
    )
    (net (code "37") (name "Net-(U12-OUT)") (class "Default")
      (node (ref "R44") (pin "1") (pinfunction "1_1") (pintype "passive"))
      (node (ref "U12") (pin "5") (pinfunction "OUT_5") (pintype "output"))
    )
    (net (code "38") (name "VCC_10V") (class "Default")
      (node (ref "C37") (pin "1") (pinfunction "1_1") (pintype "passive"))
      (node (ref "C38") (pin "1") (pinfunction "1_1") (pintype "passive"))
      (node (ref "C39") (pin "1") (pinfunction "1_1") (pintype "passive"))
      (node (ref "C40") (pin "2") (pinfunction "2_2") (pintype "passive"))
      (node (ref "D14") (pin "2") (pinfunction "A_2") (pintype "passive"))
      (node (ref "D15") (pin "2") (pinfunction "A_2") (pintype "passive"))
      (node (ref "U11") (pin "1") (pinfunction "VDD_1") (pintype "power_in"))
      (node (ref "U12") (pin "1") (pinfunction "VDD_1") (pintype "power_in"))
      (node (ref "U13") (pin "1") (pinfunction "VDD_1") (pintype "power_in"))
      (node (ref "U14") (pin "1") (pinfunction "VDD_1") (pintype "power_in"))
    )
  )
)
